# SON_versept2017.net
KiCad netlist of a schematic drawn in Altium Designer
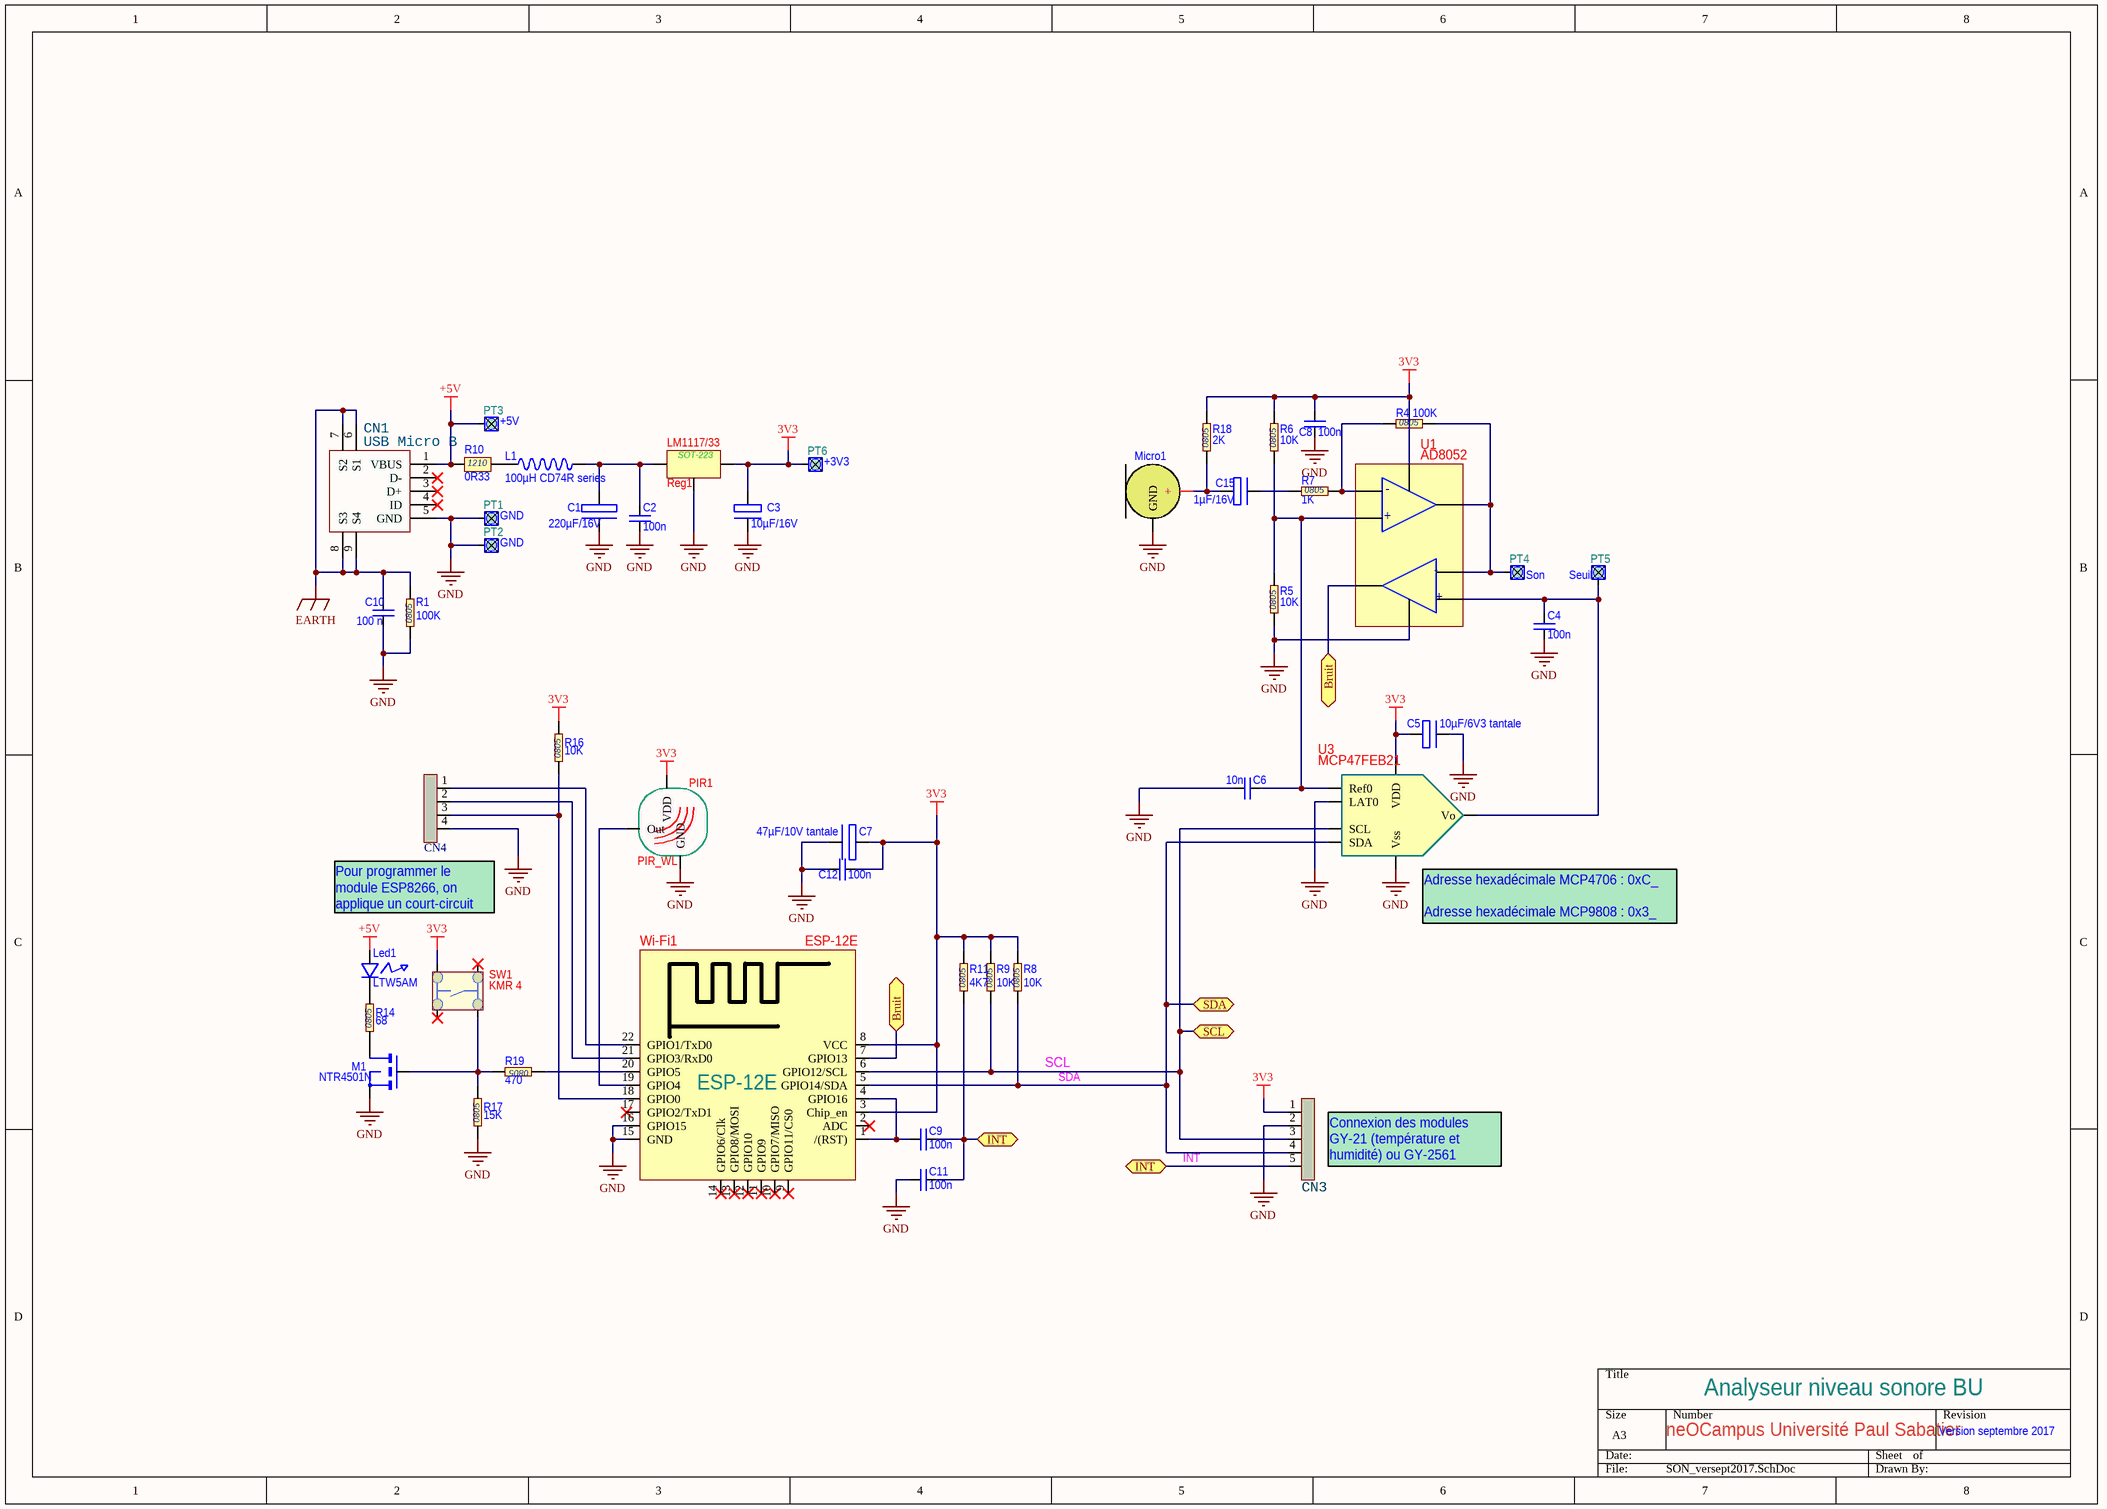
[diagram p0: SON_versept2017.SchDoc]

(export (version "E")
  (design (tool "Eeschema 10.0.6"))
  (components
    (comp (ref "C1")
      (value "220µF/16V")
      (footprint "7343-31")
      (description "253-5290 case 7343-31")
      (libsource (lib "CMS") (part "tantale 220µF/16V"))
    )
    (comp (ref "C2")
      (value "100n")
      (footprint "0805")
      (description "CMS 0805")
      (libsource (lib "CMS") (part "Cap_CMS_0805"))
    )
    (comp (ref "C3")
      (value "10µF/16V")
      (footprint "Tantale 10µF/16V")
      (description "145-7461 case 3216-18")
      (libsource (lib "CMS") (part "tantale 10µF/16V"))
    )
    (comp (ref "C4")
      (value "100n")
      (footprint "0805")
      (description "CMS 0805")
      (libsource (lib "CMS") (part "Cap_CMS_0805"))
    )
    (comp (ref "C5")
      (value "10µF/6V3 tantale")
      (footprint "Tantale 10µF/6V3")
      (description "175-4041 ou 145-7412 case 3216-18")
      (libsource (lib "CMS") (part "tantale 10µF/6V3"))
    )
    (comp (ref "C6")
      (value "10n")
      (footprint "0805")
      (description "CMS 0805")
      (libsource (lib "CMS") (part "Cap_CMS_0805"))
    )
    (comp (ref "C7")
      (value "47µF/10V tantale")
      (footprint "tantale 47µF/10V")
      (description "175-4168")
      (libsource (lib "CMS") (part "tantale 47µF/10V"))
    )
    (comp (ref "C8")
      (value "100n")
      (footprint "0805")
      (description "CMS 0805")
      (libsource (lib "CMS") (part "Cap_CMS_0805"))
    )
    (comp (ref "C9")
      (value "100n")
      (footprint "0805")
      (description "CMS 0805")
      (libsource (lib "CMS") (part "Cap_CMS_0805"))
    )
    (comp (ref "C10")
      (value "100 n")
      (footprint "0805")
      (description "CMS 0805")
      (libsource (lib "CMS") (part "Cap_CMS_0805"))
    )
    (comp (ref "C11")
      (value "100n")
      (footprint "0805")
      (description "CMS 0805")
      (libsource (lib "CMS") (part "Cap_CMS_0805"))
    )
    (comp (ref "C12")
      (value "100n")
      (footprint "0805")
      (description "CMS 0805")
      (libsource (lib "CMS") (part "Cap_CMS_0805"))
    )
    (comp (ref "C15")
      (value "1µF/16V")
      (footprint "3216-18")
      (description "145-7406 case 3216-18")
      (libsource (lib "CMS") (part "tantale 1µF/16V"))
    )
    (comp (ref "CN1")
      (value "USB Micro B")
      (footprint "USB Micro 714-2347")
      (description "Amphenol 714-2347")
      (libsource (lib "Connecteurs Contacts") (part "USB Micro B"))
    )
    (comp (ref "CN3")
      (value "inch_ligne 1x5")
      (footprint "INCH_1x5_droit")
      (description "Inch_1x5_droit")
      (libsource (lib "Connecteurs Contacts") (part "Inch_1x5_droit"))
    )
    (comp (ref "CN4")
      (value "inch_ligne 1x4")
      (footprint "INCH_1x4_droit")
      (description "Inch_1x4_droit")
      (libsource (lib "Connecteurs Contacts") (part "Inch_1x4_droit"))
    )
    (comp (ref "L1")
      (value "100µH CD74R series")
      (footprint "SELF CD74R")
      (description "SMT CD74R Aliexpress")
      (libsource (lib "CMS") (part "Self CD74R"))
    )
    (comp (ref "Led1")
      (value "LTW5AM")
      (footprint "LTW5AM")
      (description "LED Golden Dragon Plus")
      (libsource (lib "CMS") (part "LTW5AM LED"))
    )
    (comp (ref "M1")
      (value "NTR4501N")
      (footprint "SOT23 (NTR4501)")
      (description "MOSFET canal N")
      (libsource (lib "Transistors Bip Mos IGBT") (part "NTR4501N"))
    )
    (comp (ref "Micro1")
      (value "Electret")
      (footprint "Micro_electret simple")
      (description "Microphone électret")
      (libsource (lib "traversants") (part "Microphone_03"))
    )
    (comp (ref "PIR1")
      (value "PIR_WL")
      (footprint "PIR_WL")
      (description "Détecteur infrarouge")
      (libsource (lib "traversants") (part "PIR_01"))
    )
    (comp (ref "PT1")
      (value "GND")
      (footprint "PTEST boucle")
      (description "pointe de test CI 262-2179")
      (libsource (lib "Connecteurs Contacts") (part "PTEST boucle"))
    )
    (comp (ref "PT2")
      (value "GND")
      (footprint "PTEST boucle")
      (description "pointe de test CI 262-2179")
      (libsource (lib "Connecteurs Contacts") (part "PTEST boucle"))
    )
    (comp (ref "PT3")
      (value "+5V")
      (footprint "PTEST boucle")
      (description "pointe de test CI 262-2179")
      (libsource (lib "Connecteurs Contacts") (part "PTEST boucle"))
    )
    (comp (ref "PT4")
      (value "Son")
      (footprint "PTEST boucle")
      (description "pointe de test CI 262-2179")
      (libsource (lib "Connecteurs Contacts") (part "PTEST boucle"))
    )
    (comp (ref "PT5")
      (value "Seuil")
      (footprint "PTEST boucle")
      (description "pointe de test CI 262-2179")
      (libsource (lib "Connecteurs Contacts") (part "PTEST boucle"))
    )
    (comp (ref "PT6")
      (value "+3V3")
      (footprint "PTEST boucle")
      (description "pointe de test CI 262-2179")
      (libsource (lib "Connecteurs Contacts") (part "PTEST boucle"))
    )
    (comp (ref "R1")
      (value "100K")
      (footprint "0805")
      (description "CMS 0805")
      (libsource (lib "") (part "Res CMS 0805_1"))
    )
    (comp (ref "R4")
      (value "100K")
      (footprint "0805")
      (description "CMS 0805")
      (libsource (lib "CMS") (part "Res CMS 0805"))
    )
    (comp (ref "R5")
      (value "10K")
      (footprint "0805")
      (description "CMS 0805")
      (libsource (lib "") (part "Res CMS 0805_1"))
    )
    (comp (ref "R6")
      (value "10K")
      (footprint "0805")
      (description "CMS 0805")
      (libsource (lib "") (part "Res CMS 0805_1"))
    )
    (comp (ref "R7")
      (value "1K")
      (footprint "0805")
      (description "CMS 0805")
      (libsource (lib "CMS") (part "Res CMS 0805"))
    )
    (comp (ref "R8")
      (value "10K")
      (footprint "0805")
      (description "CMS 0805")
      (libsource (lib "") (part "Res CMS 0805_1"))
    )
    (comp (ref "R9")
      (value "10K")
      (footprint "0805")
      (description "CMS 0805")
      (libsource (lib "") (part "Res CMS 0805_1"))
    )
    (comp (ref "R10")
      (value "0R33")
      (footprint "1210")
      (description "CMS 1210")
      (libsource (lib "CMS") (part "Res CMS 1210 ERJ14B"))
    )
    (comp (ref "R11")
      (value "4K7")
      (footprint "0805")
      (description "CMS 0805")
      (libsource (lib "") (part "Res CMS 0805_1"))
    )
    (comp (ref "R14")
      (value "68")
      (footprint "0805")
      (description "CMS 0805")
      (libsource (lib "") (part "Res CMS 0805_1"))
    )
    (comp (ref "R16")
      (value "10K")
      (footprint "0805")
      (description "CMS 0805")
      (libsource (lib "") (part "Res CMS 0805_1"))
    )
    (comp (ref "R17")
      (value "15K")
      (footprint "0805")
      (description "CMS 0805")
      (libsource (lib "") (part "Res CMS 0805_1"))
    )
    (comp (ref "R18")
      (value "2K")
      (footprint "0805")
      (description "CMS 0805")
      (libsource (lib "") (part "Res CMS 0805_1"))
    )
    (comp (ref "R19")
      (value "470")
      (footprint "0805")
      (description "CMS 0805")
      (libsource (lib "") (part "Res CMS 0805_2"))
    )
    (comp (ref "Reg1")
      (value "LM1117/33")
      (footprint "SOT-223 thermo1")
      (description "Régulateur SOT-223")
      (libsource (lib "Convertisseurs_Régulateurs") (part "LM1117MPX-3.3"))
    )
    (comp (ref "SW1")
      (value "KMR 4")
      (footprint "µSwitch KMR4")
      (description "KMR 4 Series 793-1605")
      (libsource (lib "Interrupteurs Commutateurs") (part "µSwitch"))
    )
    (comp (ref "U1")
      (value "AD8052")
      (footprint "SOIC08")
      (description "AOP")
      (libsource (lib "CMS") (part "AD8052"))
    )
    (comp (ref "U3")
      (value "MCP47FEB21")
      (footprint "TSSOP_8")
      (description "DAC I2C (RS : 879-3261)")
      (libsource (lib "CMS") (part "MCP47FEB21"))
    )
    (comp (ref "Wi-Fi1")
      (value "ESP-12E")
      (footprint "ESP-12E")
      (description "ESP-12E module Wi-Fi")
      (libsource (lib "CMS") (part "ESP-12E"))
    )
  )
  (nets
    (net (code "1") (name "+5V") (class "Default")
      (node (ref "CN1") (pin "1") (pinfunction "VBUS_1") (pintype "passive"))
      (node (ref "Led1") (pin "1") (pinfunction "anode_1") (pintype "passive"))
      (node (ref "PT3") (pin "1") (pinfunction "PIN_1") (pintype "passive"))
      (node (ref "R10") (pin "1") (pinfunction "CT1_1") (pintype "passive"))
    )
    (net (code "2") (name "/Bruit") (class "Default")
      (node (ref "U1") (pin "7") (pinfunction "out_7") (pintype "passive"))
      (node (ref "Wi-Fi1") (pin "7") (pinfunction "GPIO13_7") (pintype "passive"))
    )
    (net (code "3") (name "/INT") (class "Default")
      (node (ref "C11") (pin "2") (pinfunction "CT2_2") (pintype "passive"))
      (node (ref "C9") (pin "1") (pinfunction "CT1_1") (pintype "passive"))
      (node (ref "CN3") (pin "5") (pintype "passive"))
      (node (ref "R11") (pin "1") (pinfunction "CT1_1") (pintype "passive"))
    )
    (net (code "4") (name "/SCL") (class "Default")
      (node (ref "CN3") (pin "3") (pintype "passive"))
      (node (ref "R9") (pin "1") (pinfunction "CT1_1") (pintype "passive"))
      (node (ref "U3") (pin "7") (pinfunction "SCL_7") (pintype "passive"))
      (node (ref "Wi-Fi1") (pin "6") (pinfunction "GPIO12/SCL_6") (pintype "passive"))
    )
    (net (code "5") (name "/SDA") (class "Default")
      (node (ref "CN3") (pin "4") (pintype "passive"))
      (node (ref "R8") (pin "1") (pinfunction "CT1_1") (pintype "passive"))
      (node (ref "U3") (pin "8") (pinfunction "SDA_8") (pintype "passive"))
      (node (ref "Wi-Fi1") (pin "5") (pinfunction "GPIO14/SDA_5") (pintype "passive"))
    )
    (net (code "6") (name "3V3") (class "Default")
      (node (ref "C12") (pin "2") (pinfunction "CT2_2") (pintype "passive"))
      (node (ref "C3") (pin "1") (pinfunction "V+_1") (pintype "passive"))
      (node (ref "C5") (pin "1") (pinfunction "V+_1") (pintype "passive"))
      (node (ref "C7") (pin "1") (pinfunction "V+_1") (pintype "passive"))
      (node (ref "C8") (pin "2") (pinfunction "CT2_2") (pintype "passive"))
      (node (ref "CN3") (pin "1") (pintype "passive"))
      (node (ref "PIR1") (pin "1") (pinfunction "VDD_1") (pintype "passive"))
      (node (ref "PT6") (pin "1") (pinfunction "PIN_1") (pintype "passive"))
      (node (ref "R11") (pin "2") (pinfunction "CT2_2") (pintype "passive"))
      (node (ref "R16") (pin "2") (pinfunction "CT2_2") (pintype "passive"))
      (node (ref "R18") (pin "2") (pinfunction "CT2_2") (pintype "passive"))
      (node (ref "R6") (pin "2") (pinfunction "CT2_2") (pintype "passive"))
      (node (ref "R8") (pin "2") (pinfunction "CT2_2") (pintype "passive"))
      (node (ref "R9") (pin "2") (pinfunction "CT2_2") (pintype "passive"))
      (node (ref "Reg1") (pin "2") (pinfunction "OUT_2") (pintype "passive"))
      (node (ref "SW1") (pin "2") (pinfunction "CT2_2") (pintype "passive"))
      (node (ref "U1") (pin "8") (pinfunction "V+_8") (pintype "passive"))
      (node (ref "U3") (pin "1") (pinfunction "VDD_1") (pintype "passive"))
      (node (ref "Wi-Fi1") (pin "3") (pinfunction "Chip_en_3") (pintype "passive"))
      (node (ref "Wi-Fi1") (pin "8") (pinfunction "VCC_8") (pintype "passive"))
    )
    (net (code "7") (name "EARTH") (class "Default")
      (node (ref "C10") (pin "2") (pinfunction "CT2_2") (pintype "passive"))
      (node (ref "CN1") (pin "6") (pinfunction "S1_6") (pintype "passive"))
      (node (ref "CN1") (pin "7") (pinfunction "S2_7") (pintype "passive"))
      (node (ref "CN1") (pin "8") (pinfunction "S3_8") (pintype "passive"))
      (node (ref "CN1") (pin "9") (pinfunction "S4_9") (pintype "passive"))
      (node (ref "R1") (pin "2") (pinfunction "CT2_2") (pintype "passive"))
    )
    (net (code "8") (name "GND") (class "Default")
      (node (ref "C1") (pin "2") (pinfunction "V-_2") (pintype "passive"))
      (node (ref "C10") (pin "1") (pinfunction "CT1_1") (pintype "passive"))
      (node (ref "C11") (pin "1") (pinfunction "CT1_1") (pintype "passive"))
      (node (ref "C12") (pin "1") (pinfunction "CT1_1") (pintype "passive"))
      (node (ref "C2") (pin "1") (pinfunction "CT1_1") (pintype "passive"))
      (node (ref "C3") (pin "2") (pinfunction "V-_2") (pintype "passive"))
      (node (ref "C4") (pin "1") (pinfunction "CT1_1") (pintype "passive"))
      (node (ref "C5") (pin "2") (pinfunction "V-_2") (pintype "passive"))
      (node (ref "C6") (pin "2") (pinfunction "CT2_2") (pintype "passive"))
      (node (ref "C7") (pin "2") (pinfunction "V-_2") (pintype "passive"))
      (node (ref "C8") (pin "1") (pinfunction "CT1_1") (pintype "passive"))
      (node (ref "CN1") (pin "5") (pinfunction "GND_5") (pintype "passive"))
      (node (ref "CN3") (pin "2") (pintype "passive"))
      (node (ref "CN4") (pin "4") (pintype "passive"))
      (node (ref "M1") (pin "3") (pinfunction "S_3") (pintype "passive"))
      (node (ref "Micro1") (pin "0") (pinfunction "GND_0") (pintype "passive"))
      (node (ref "PIR1") (pin "3") (pinfunction "GND_3") (pintype "passive"))
      (node (ref "PT1") (pin "1") (pinfunction "PIN_1") (pintype "passive"))
      (node (ref "PT2") (pin "1") (pinfunction "PIN_1") (pintype "passive"))
      (node (ref "R1") (pin "1") (pinfunction "CT1_1") (pintype "passive"))
      (node (ref "R17") (pin "1") (pinfunction "CT1_1") (pintype "passive"))
      (node (ref "R5") (pin "1") (pinfunction "CT1_1") (pintype "passive"))
      (node (ref "Reg1") (pin "1") (pinfunction "GND_1") (pintype "passive"))
      (node (ref "U1") (pin "4") (pinfunction "V-_4") (pintype "passive"))
      (node (ref "U3") (pin "5") (pinfunction "Vss_5") (pintype "passive"))
      (node (ref "U3") (pin "6") (pinfunction "LAT0_6") (pintype "passive"))
      (node (ref "Wi-Fi1") (pin "15") (pinfunction "GND_15") (pintype "passive"))
      (node (ref "Wi-Fi1") (pin "16") (pinfunction "GPIO15_16") (pintype "passive"))
    )
    (net (code "9") (name "Net-(C1-V+)") (class "Default")
      (node (ref "C1") (pin "1") (pinfunction "V+_1") (pintype "passive"))
      (node (ref "C2") (pin "2") (pinfunction "CT2_2") (pintype "passive"))
      (node (ref "L1") (pin "1") (pinfunction "CT1_1") (pintype "passive"))
      (node (ref "Reg1") (pin "3") (pinfunction "IN_3") (pintype "passive"))
    )
    (net (code "10") (name "Net-(C4-CT2)") (class "Default")
      (node (ref "C4") (pin "2") (pinfunction "CT2_2") (pintype "passive"))
      (node (ref "PT5") (pin "1") (pinfunction "PIN_1") (pintype "passive"))
      (node (ref "U1") (pin "5") (pinfunction "in+_5") (pintype "passive"))
      (node (ref "U3") (pin "3") (pinfunction "Vo_3") (pintype "passive"))
    )
    (net (code "11") (name "Net-(C6-CT1)") (class "Default")
      (node (ref "C6") (pin "1") (pinfunction "CT1_1") (pintype "passive"))
      (node (ref "R5") (pin "2") (pinfunction "CT2_2") (pintype "passive"))
      (node (ref "R6") (pin "1") (pinfunction "CT1_1") (pintype "passive"))
      (node (ref "U1") (pin "3") (pinfunction "in+_3") (pintype "passive"))
      (node (ref "U3") (pin "2") (pinfunction "Ref0_2") (pintype "passive"))
    )
    (net (code "12") (name "Net-(C9-CT2)") (class "Default")
      (node (ref "C9") (pin "2") (pinfunction "CT2_2") (pintype "passive"))
      (node (ref "Wi-Fi1") (pin "1") (pinfunction "/(RST)_1") (pintype "passive"))
      (node (ref "Wi-Fi1") (pin "4") (pinfunction "GPIO16_4") (pintype "passive"))
    )
    (net (code "13") (name "Net-(C15-V+)") (class "Default")
      (node (ref "C15") (pin "1") (pinfunction "V+_1") (pintype "passive"))
      (node (ref "Micro1") (pin "1") (pinfunction "+_1") (pintype "passive"))
      (node (ref "R18") (pin "1") (pinfunction "CT1_1") (pintype "passive"))
    )
    (net (code "14") (name "Net-(C15-V-)") (class "Default")
      (node (ref "C15") (pin "2") (pinfunction "V-_2") (pintype "passive"))
      (node (ref "R7") (pin "1") (pinfunction "CT1_1") (pintype "passive"))
    )
    (net (code "15") (name "Net-(L1-CT2)") (class "Default")
      (node (ref "L1") (pin "2") (pinfunction "CT2_2") (pintype "passive"))
      (node (ref "R10") (pin "2") (pinfunction "CT2_2") (pintype "passive"))
    )
    (net (code "16") (name "Net-(Led1-cathode)") (class "Default")
      (node (ref "Led1") (pin "2") (pinfunction "cathode_2") (pintype "passive"))
      (node (ref "R14") (pin "2") (pinfunction "CT2_2") (pintype "passive"))
    )
    (net (code "17") (name "Net-(M1-D)") (class "Default")
      (node (ref "M1") (pin "1") (pinfunction "D_1") (pintype "passive"))
      (node (ref "R14") (pin "1") (pinfunction "CT1_1") (pintype "passive"))
    )
    (net (code "18") (name "Net-(M1-G)") (class "Default")
      (node (ref "M1") (pin "2") (pinfunction "G_2") (pintype "passive"))
      (node (ref "R17") (pin "2") (pinfunction "CT2_2") (pintype "passive"))
      (node (ref "R19") (pin "2") (pinfunction "CT2_2") (pintype "passive"))
      (node (ref "SW1") (pin "3") (pinfunction "CT3_3") (pintype "passive"))
    )
    (net (code "19") (name "Net-(PIR1-Out)") (class "Default")
      (node (ref "PIR1") (pin "2") (pinfunction "Out_2") (pintype "passive"))
      (node (ref "Wi-Fi1") (pin "19") (pinfunction "GPIO4_19") (pintype "passive"))
    )
    (net (code "20") (name "Net-(PT4-PIN)") (class "Default")
      (node (ref "PT4") (pin "1") (pinfunction "PIN_1") (pintype "passive"))
      (node (ref "R4") (pin "2") (pinfunction "CT2_2") (pintype "passive"))
      (node (ref "U1") (pin "1") (pinfunction "out_1") (pintype "passive"))
      (node (ref "U1") (pin "6") (pinfunction "in-_6") (pintype "passive"))
    )
    (net (code "21") (name "Net-(R4-CT1)") (class "Default")
      (node (ref "R4") (pin "1") (pinfunction "CT1_1") (pintype "passive"))
      (node (ref "R7") (pin "2") (pinfunction "CT2_2") (pintype "passive"))
      (node (ref "U1") (pin "2") (pinfunction "in-_2") (pintype "passive"))
    )
    (net (code "22") (name "Net-(R16-CT1)") (class "Default")
      (node (ref "CN4") (pin "3") (pintype "passive"))
      (node (ref "R16") (pin "1") (pinfunction "CT1_1") (pintype "passive"))
      (node (ref "Wi-Fi1") (pin "18") (pinfunction "GPIO0_18") (pintype "passive"))
    )
    (net (code "23") (name "Net-(R19-CT1)") (class "Default")
      (node (ref "R19") (pin "1") (pinfunction "CT1_1") (pintype "passive"))
      (node (ref "Wi-Fi1") (pin "20") (pinfunction "GPIO5_20") (pintype "passive"))
    )
    (net (code "24") (name "Net-(Wi-Fi1-GPIO1{slash}TxD0)") (class "Default")
      (node (ref "CN4") (pin "1") (pintype "passive"))
      (node (ref "Wi-Fi1") (pin "22") (pinfunction "GPIO1/TxD0_22") (pintype "passive"))
    )
    (net (code "25") (name "Net-(Wi-Fi1-GPIO3{slash}RxD0)") (class "Default")
      (node (ref "CN4") (pin "2") (pintype "passive"))
      (node (ref "Wi-Fi1") (pin "21") (pinfunction "GPIO3/RxD0_21") (pintype "passive"))
    )
    (net (code "26") (name "unconnected-(CN1-D+-Pad3)") (class "Default")
      (node (ref "CN1") (pin "3") (pinfunction "D+_3") (pintype "passive+no_connect"))
    )
    (net (code "27") (name "unconnected-(CN1-D--Pad2)") (class "Default")
      (node (ref "CN1") (pin "2") (pinfunction "D-_2") (pintype "passive+no_connect"))
    )
    (net (code "28") (name "unconnected-(CN1-ID-Pad4)") (class "Default")
      (node (ref "CN1") (pin "4") (pinfunction "ID_4") (pintype "passive+no_connect"))
    )
    (net (code "29") (name "unconnected-(SW1-CT1-Pad1)") (class "Default")
      (node (ref "SW1") (pin "1") (pinfunction "CT1_1") (pintype "passive+no_connect"))
    )
    (net (code "30") (name "unconnected-(SW1-CT4-Pad4)") (class "Default")
      (node (ref "SW1") (pin "4") (pinfunction "CT4_4") (pintype "passive+no_connect"))
    )
    (net (code "31") (name "unconnected-(Wi-Fi1-ADC-Pad2)") (class "Default")
      (node (ref "Wi-Fi1") (pin "2") (pinfunction "ADC_2") (pintype "passive+no_connect"))
    )
    (net (code "32") (name "unconnected-(Wi-Fi1-GPIO2{slash}TxD1-Pad17)") (class "Default")
      (node (ref "Wi-Fi1") (pin "17") (pinfunction "GPIO2/TxD1_17") (pintype "passive+no_connect"))
    )
    (net (code "33") (name "unconnected-(Wi-Fi1-GPIO6{slash}Clk-Pad14)") (class "Default")
      (node (ref "Wi-Fi1") (pin "14") (pinfunction "GPIO6/Clk_14") (pintype "passive+no_connect"))
    )
    (net (code "34") (name "unconnected-(Wi-Fi1-GPIO7{slash}MISO-Pad10)") (class "Default")
      (node (ref "Wi-Fi1") (pin "10") (pinfunction "GPIO7/MISO_10") (pintype "passive+no_connect"))
    )
    (net (code "35") (name "unconnected-(Wi-Fi1-GPIO8{slash}MOSI-Pad13)") (class "Default")
      (node (ref "Wi-Fi1") (pin "13") (pinfunction "GPIO8/MOSI_13") (pintype "passive+no_connect"))
    )
    (net (code "36") (name "unconnected-(Wi-Fi1-GPIO9-Pad11)") (class "Default")
      (node (ref "Wi-Fi1") (pin "11") (pinfunction "GPIO9_11") (pintype "passive+no_connect"))
    )
    (net (code "37") (name "unconnected-(Wi-Fi1-GPIO10-Pad12)") (class "Default")
      (node (ref "Wi-Fi1") (pin "12") (pinfunction "GPIO10_12") (pintype "passive+no_connect"))
    )
    (net (code "38") (name "unconnected-(Wi-Fi1-GPIO11{slash}CS0-Pad9)") (class "Default")
      (node (ref "Wi-Fi1") (pin "9") (pinfunction "GPIO11/CS0_9") (pintype "passive+no_connect"))
    )
  )
)
